# exp2.net
KiCad netlist of a schematic drawn in EAGLE
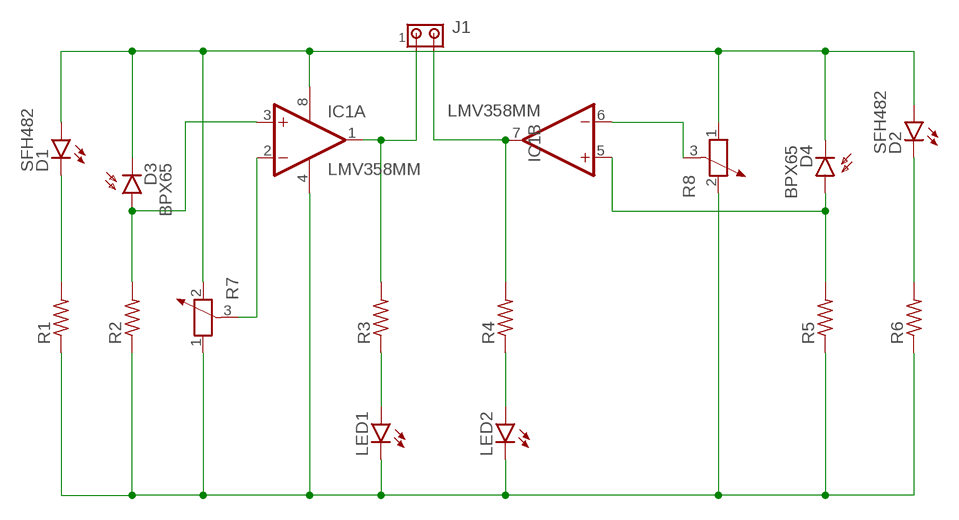
[diagram p0: schematic, sheet 1]

(export (version "E")
  (design (tool "Eeschema 10.0.6"))
  (components
    (comp (ref "D1")
      (value "SFH482")
      (footprint "eagle-import:SFH482")
      (libsource (lib "eagle-import") (part "SFH482"))
    )
    (comp (ref "D2")
      (value "SFH482")
      (footprint "eagle-import:SFH482")
      (libsource (lib "eagle-import") (part "SFH482"))
    )
    (comp (ref "D3")
      (value "BPX65")
      (footprint "eagle-import:BPX65")
      (fields (field (name "MPN") "BPX65."))
      (libsource (lib "eagle-import") (part "BPX65"))
    )
    (comp (ref "D4")
      (value "BPX65")
      (footprint "eagle-import:BPX65")
      (fields (field (name "MPN") "BPX65."))
      (libsource (lib "eagle-import") (part "BPX65"))
    )
    (comp (ref "IC1")
      (value "LMV358MM")
      (footprint "eagle-import:MSOP08")
      (libsource (lib "eagle-import") (part "LMV358?MM"))
    )
    (comp (ref "J1")
      (value "MTA02-100")
      (footprint "eagle-import:10X02MTA")
      (libsource (lib "eagle-import") (part "MTA02-100"))
    )
    (comp (ref "LED1")
      (value "LED3MM")
      (footprint "eagle-import:LED3MM")
      (libsource (lib "eagle-import") (part "LED3MM"))
    )
    (comp (ref "LED2")
      (value "LED3MM")
      (footprint "eagle-import:LED3MM")
      (libsource (lib "eagle-import") (part "LED3MM"))
    )
    (comp (ref "R1")
      (value "R-US_0204/5")
      (footprint "eagle-import:0204_5")
      (libsource (lib "eagle-import") (part "R-US_0204/5"))
    )
    (comp (ref "R2")
      (value "R-US_0204/5")
      (footprint "eagle-import:0204_5")
      (libsource (lib "eagle-import") (part "R-US_0204/5"))
    )
    (comp (ref "R3")
      (value "R-US_0204/5")
      (footprint "eagle-import:0204_5")
      (libsource (lib "eagle-import") (part "R-US_0204/5"))
    )
    (comp (ref "R4")
      (value "R-US_0204/5")
      (footprint "eagle-import:0204_5")
      (libsource (lib "eagle-import") (part "R-US_0204/5"))
    )
    (comp (ref "R5")
      (value "R-US_0204/5")
      (footprint "eagle-import:0204_5")
      (libsource (lib "eagle-import") (part "R-US_0204/5"))
    )
    (comp (ref "R6")
      (value "R-US_0204/5")
      (footprint "eagle-import:0204_5")
      (libsource (lib "eagle-import") (part "R-US_0204/5"))
    )
    (comp (ref "R7")
      (value "POTENTIOMETER_PT-10")
      (footprint "eagle-import:PT-10")
      (libsource (lib "eagle-import") (part "POTENTIOMETER_PT-10"))
    )
    (comp (ref "R8")
      (value "POTENTIOMETER_PT-10")
      (footprint "eagle-import:PT-10")
      (libsource (lib "eagle-import") (part "POTENTIOMETER_PT-10"))
    )
  )
  (nets
    (net (code "1") (name "Net-(D1-C)") (class "Default")
      (node (ref "D1") (pin "K") (pinfunction "C_K") (pintype "passive"))
      (node (ref "R1") (pin "2") (pinfunction "2_2") (pintype "passive"))
    )
    (net (code "2") (name "Net-(D2-C)") (class "Default")
      (node (ref "D2") (pin "K") (pinfunction "C_K") (pintype "passive"))
      (node (ref "R6") (pin "2") (pinfunction "2_2") (pintype "passive"))
    )
    (net (code "3") (name "Net-(D3-C)") (class "Default")
      (node (ref "D1") (pin "A") (pinfunction "A_A") (pintype "passive"))
      (node (ref "D2") (pin "A") (pinfunction "A_A") (pintype "passive"))
      (node (ref "D3") (pin "K") (pinfunction "C_K") (pintype "passive"))
      (node (ref "D4") (pin "K") (pinfunction "C_K") (pintype "passive"))
      (node (ref "IC1") (pin "8") (pinfunction "V+_8") (pintype "power_in"))
      (node (ref "R7") (pin "2") (pinfunction "2_2") (pintype "passive"))
      (node (ref "R8") (pin "1") (pinfunction "1_1") (pintype "passive"))
    )
    (net (code "4") (name "Net-(IC1A-+IN)") (class "Default")
      (node (ref "D3") (pin "A") (pinfunction "A_A") (pintype "passive"))
      (node (ref "IC1") (pin "3") (pinfunction "+IN_3") (pintype "input"))
      (node (ref "R2") (pin "2") (pinfunction "2_2") (pintype "passive"))
    )
    (net (code "5") (name "Net-(IC1A--IN)") (class "Default")
      (node (ref "IC1") (pin "2") (pinfunction "-IN_2") (pintype "input"))
      (node (ref "R7") (pin "3") (pinfunction "3_3") (pintype "passive"))
    )
    (net (code "6") (name "Net-(IC1A-OUT)") (class "Default")
      (node (ref "IC1") (pin "1") (pinfunction "OUT_1") (pintype "output"))
      (node (ref "J1") (pin "1") (pinfunction "1_1") (pintype "passive"))
      (node (ref "R3") (pin "2") (pinfunction "2_2") (pintype "passive"))
    )
    (net (code "7") (name "Net-(IC1B-+IN)") (class "Default")
      (node (ref "D4") (pin "A") (pinfunction "A_A") (pintype "passive"))
      (node (ref "IC1") (pin "5") (pinfunction "+IN_5") (pintype "input"))
      (node (ref "R5") (pin "2") (pinfunction "2_2") (pintype "passive"))
    )
    (net (code "8") (name "Net-(IC1B--IN)") (class "Default")
      (node (ref "IC1") (pin "6") (pinfunction "-IN_6") (pintype "input"))
      (node (ref "R8") (pin "3") (pinfunction "3_3") (pintype "passive"))
    )
    (net (code "9") (name "Net-(IC1B-OUT)") (class "Default")
      (node (ref "IC1") (pin "7") (pinfunction "OUT_7") (pintype "output"))
      (node (ref "J1") (pin "2") (pinfunction "2_2") (pintype "passive"))
      (node (ref "R4") (pin "2") (pinfunction "2_2") (pintype "passive"))
    )
    (net (code "10") (name "Net-(IC1C-V-)") (class "Default")
      (node (ref "IC1") (pin "4") (pinfunction "V-_4") (pintype "power_in"))
      (node (ref "LED1") (pin "K") (pinfunction "C_K") (pintype "passive"))
      (node (ref "LED2") (pin "K") (pinfunction "C_K") (pintype "passive"))
      (node (ref "R1") (pin "1") (pinfunction "1_1") (pintype "passive"))
      (node (ref "R2") (pin "1") (pinfunction "1_1") (pintype "passive"))
      (node (ref "R5") (pin "1") (pinfunction "1_1") (pintype "passive"))
      (node (ref "R6") (pin "1") (pinfunction "1_1") (pintype "passive"))
      (node (ref "R7") (pin "1") (pinfunction "1_1") (pintype "passive"))
      (node (ref "R8") (pin "2") (pinfunction "2_2") (pintype "passive"))
    )
    (net (code "11") (name "Net-(LED1-PadA)") (class "Default")
      (node (ref "LED1") (pin "A") (pinfunction "A_A") (pintype "passive"))
      (node (ref "R3") (pin "1") (pinfunction "1_1") (pintype "passive"))
    )
    (net (code "12") (name "Net-(LED2-PadA)") (class "Default")
      (node (ref "LED2") (pin "A") (pinfunction "A_A") (pintype "passive"))
      (node (ref "R4") (pin "1") (pinfunction "1_1") (pintype "passive"))
    )
  )
)
